# Sheet1.net
KiCad netlist of a schematic drawn in Altium Designer
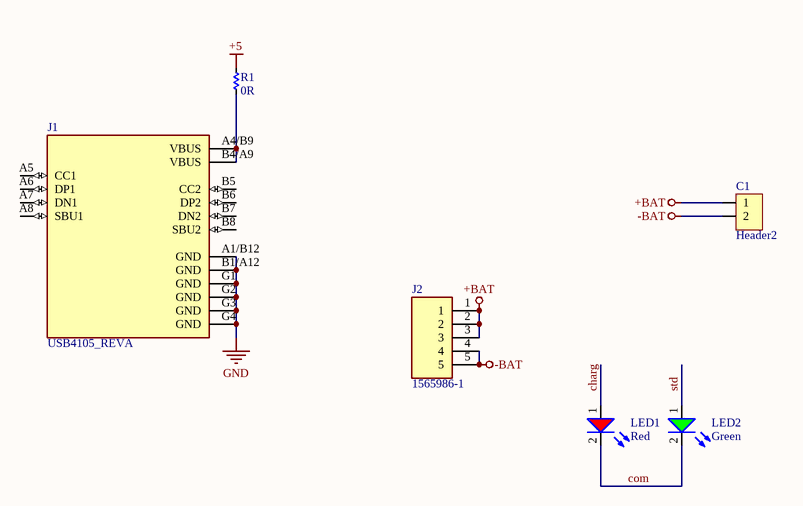
[diagram p0: Sheet1.SchDoc]

(export (version "E")
  (design (tool "Eeschema 10.0.6"))
  (components
    (comp (ref "C1")
      (value "Header2")
      (footprint "Header2")
      (description "Header IDC, 2 x 1 Pin Vertical 2.54mm Pitch (Non-Boxed, Male)")
      (fields
        (field (name "MANUFACTURER") "Würth Elektronik eiSos GmbH")
        (field (name "PARTNO") "613002143121")
        (field (name "CREATED BY") "Karrer Zheng")
      )
      (libsource (lib "TechMT.VN_Lib_Project v2") (part "Header2"))
    )
    (comp (ref "J1")
      (value "USB4105_REVA")
      (footprint "GCT_USB4105_REVA")
      (fields (field (name "MF") "Global Connector Technology") (field (name "MP") "USB4105"))
      (libsource (lib "usb_typeC2.0B") (part "USB4105_REVA"))
    )
    (comp (ref "J2")
      (value "1565986-1")
      (footprint "TE_1565986-1")
      (description "CONN RCPT 5POS 2.50MM PCB SLDR")
      (libsource (lib "1565986-1") (part "1565986-1"))
    )
    (comp (ref "LED1")
      (value "Red")
      (footprint "Led 0805R")
      (description "LED Red 2mA 1.8V 0805")
      (fields (field (name "Comment") "LED-0805RVC"))
      (libsource (lib "TechMT.VN_Lib_Project v1.0") (part "LED-0805RVC"))
    )
    (comp (ref "LED2")
      (value "Green")
      (footprint "Led 0805G")
      (description "LED Green 2mA 3V 0805")
      (fields (field (name "Comment") "LED-0805GVC"))
      (libsource (lib "TechMT.VN_Lib_Project v1.0") (part "LED-0805GVC"))
    )
    (comp (ref "R1")
      (value "0R")
      (footprint "RES-SMD-0603")
      (description "Resistor")
      (fields
        (field (name "MANUFACTURER") "Generic Components")
        (field (name "PUBLISHER") "Altium Hobart Technology Centre")
      )
      (libsource (lib "TechMT.VN_Lib_Project v2") (part "Res-SMD"))
    )
  )
  (nets
    (net (code "1") (name "+5") (class "Default")
      (node (ref "R1") (pin "1") (pinfunction "1_1") (pintype "passive"))
    )
    (net (code "2") (name "+BAT") (class "Default")
      (node (ref "C1") (pin "1") (pinfunction "1_1") (pintype "passive"))
      (node (ref "J2") (pin "1") (pinfunction "1_1") (pintype "passive"))
      (node (ref "J2") (pin "2") (pinfunction "2_2") (pintype "passive"))
      (node (ref "J2") (pin "3") (pinfunction "3_3") (pintype "passive"))
    )
    (net (code "3") (name "-BAT") (class "Default")
      (node (ref "C1") (pin "2") (pinfunction "2_2") (pintype "passive"))
      (node (ref "J2") (pin "4") (pinfunction "4_4") (pintype "passive"))
      (node (ref "J2") (pin "5") (pinfunction "5_5") (pintype "passive"))
    )
    (net (code "4") (name "/charg") (class "Default")
      (node (ref "LED1") (pin "1") (pinfunction "A_1") (pintype "passive"))
    )
    (net (code "5") (name "/com") (class "Default")
      (node (ref "LED1") (pin "2") (pinfunction "K_2") (pintype "passive"))
      (node (ref "LED2") (pin "2") (pinfunction "K_2") (pintype "passive"))
    )
    (net (code "6") (name "/std") (class "Default")
      (node (ref "LED2") (pin "1") (pinfunction "A_1") (pintype "passive"))
    )
    (net (code "7") (name "GND") (class "Default")
      (node (ref "J1") (pin "A1/B12") (pinfunction "GND_A1/B12") (pintype "power_in"))
      (node (ref "J1") (pin "B1/A12") (pinfunction "GND_B1/A12") (pintype "power_in"))
      (node (ref "J1") (pin "G1") (pinfunction "GND_G1") (pintype "power_in"))
      (node (ref "J1") (pin "G2") (pinfunction "GND_G2") (pintype "power_in"))
      (node (ref "J1") (pin "G3") (pinfunction "GND_G3") (pintype "power_in"))
      (node (ref "J1") (pin "G4") (pinfunction "GND_G4") (pintype "power_in"))
    )
    (net (code "8") (name "Net-(J1-VBUS-PadA4{slash}B9)") (class "Default")
      (node (ref "J1") (pin "A4/B9") (pinfunction "VBUS_A4/B9") (pintype "power_in"))
      (node (ref "J1") (pin "B4/A9") (pinfunction "VBUS_B4/A9") (pintype "power_in"))
      (node (ref "R1") (pin "2") (pinfunction "2_2") (pintype "passive"))
    )
    (net (code "9") (name "unconnected-(J1-CC1-PadA5)") (class "Default")
      (node (ref "J1") (pin "A5") (pinfunction "CC1_A5") (pintype "bidirectional"))
    )
    (net (code "10") (name "unconnected-(J1-CC2-PadB5)") (class "Default")
      (node (ref "J1") (pin "B5") (pinfunction "CC2_B5") (pintype "bidirectional"))
    )
    (net (code "11") (name "unconnected-(J1-DN1-PadA7)") (class "Default")
      (node (ref "J1") (pin "A7") (pinfunction "DN1_A7") (pintype "bidirectional"))
    )
    (net (code "12") (name "unconnected-(J1-DN2-PadB7)") (class "Default")
      (node (ref "J1") (pin "B7") (pinfunction "DN2_B7") (pintype "bidirectional"))
    )
    (net (code "13") (name "unconnected-(J1-DP1-PadA6)") (class "Default")
      (node (ref "J1") (pin "A6") (pinfunction "DP1_A6") (pintype "bidirectional"))
    )
    (net (code "14") (name "unconnected-(J1-DP2-PadB6)") (class "Default")
      (node (ref "J1") (pin "B6") (pinfunction "DP2_B6") (pintype "bidirectional"))
    )
    (net (code "15") (name "unconnected-(J1-SBU1-PadA8)") (class "Default")
      (node (ref "J1") (pin "A8") (pinfunction "SBU1_A8") (pintype "bidirectional"))
    )
    (net (code "16") (name "unconnected-(J1-SBU2-PadB8)") (class "Default")
      (node (ref "J1") (pin "B8") (pinfunction "SBU2_B8") (pintype "bidirectional"))
    )
  )
)
